# Mainboard.net
KiCad netlist of a schematic drawn in Altium Designer
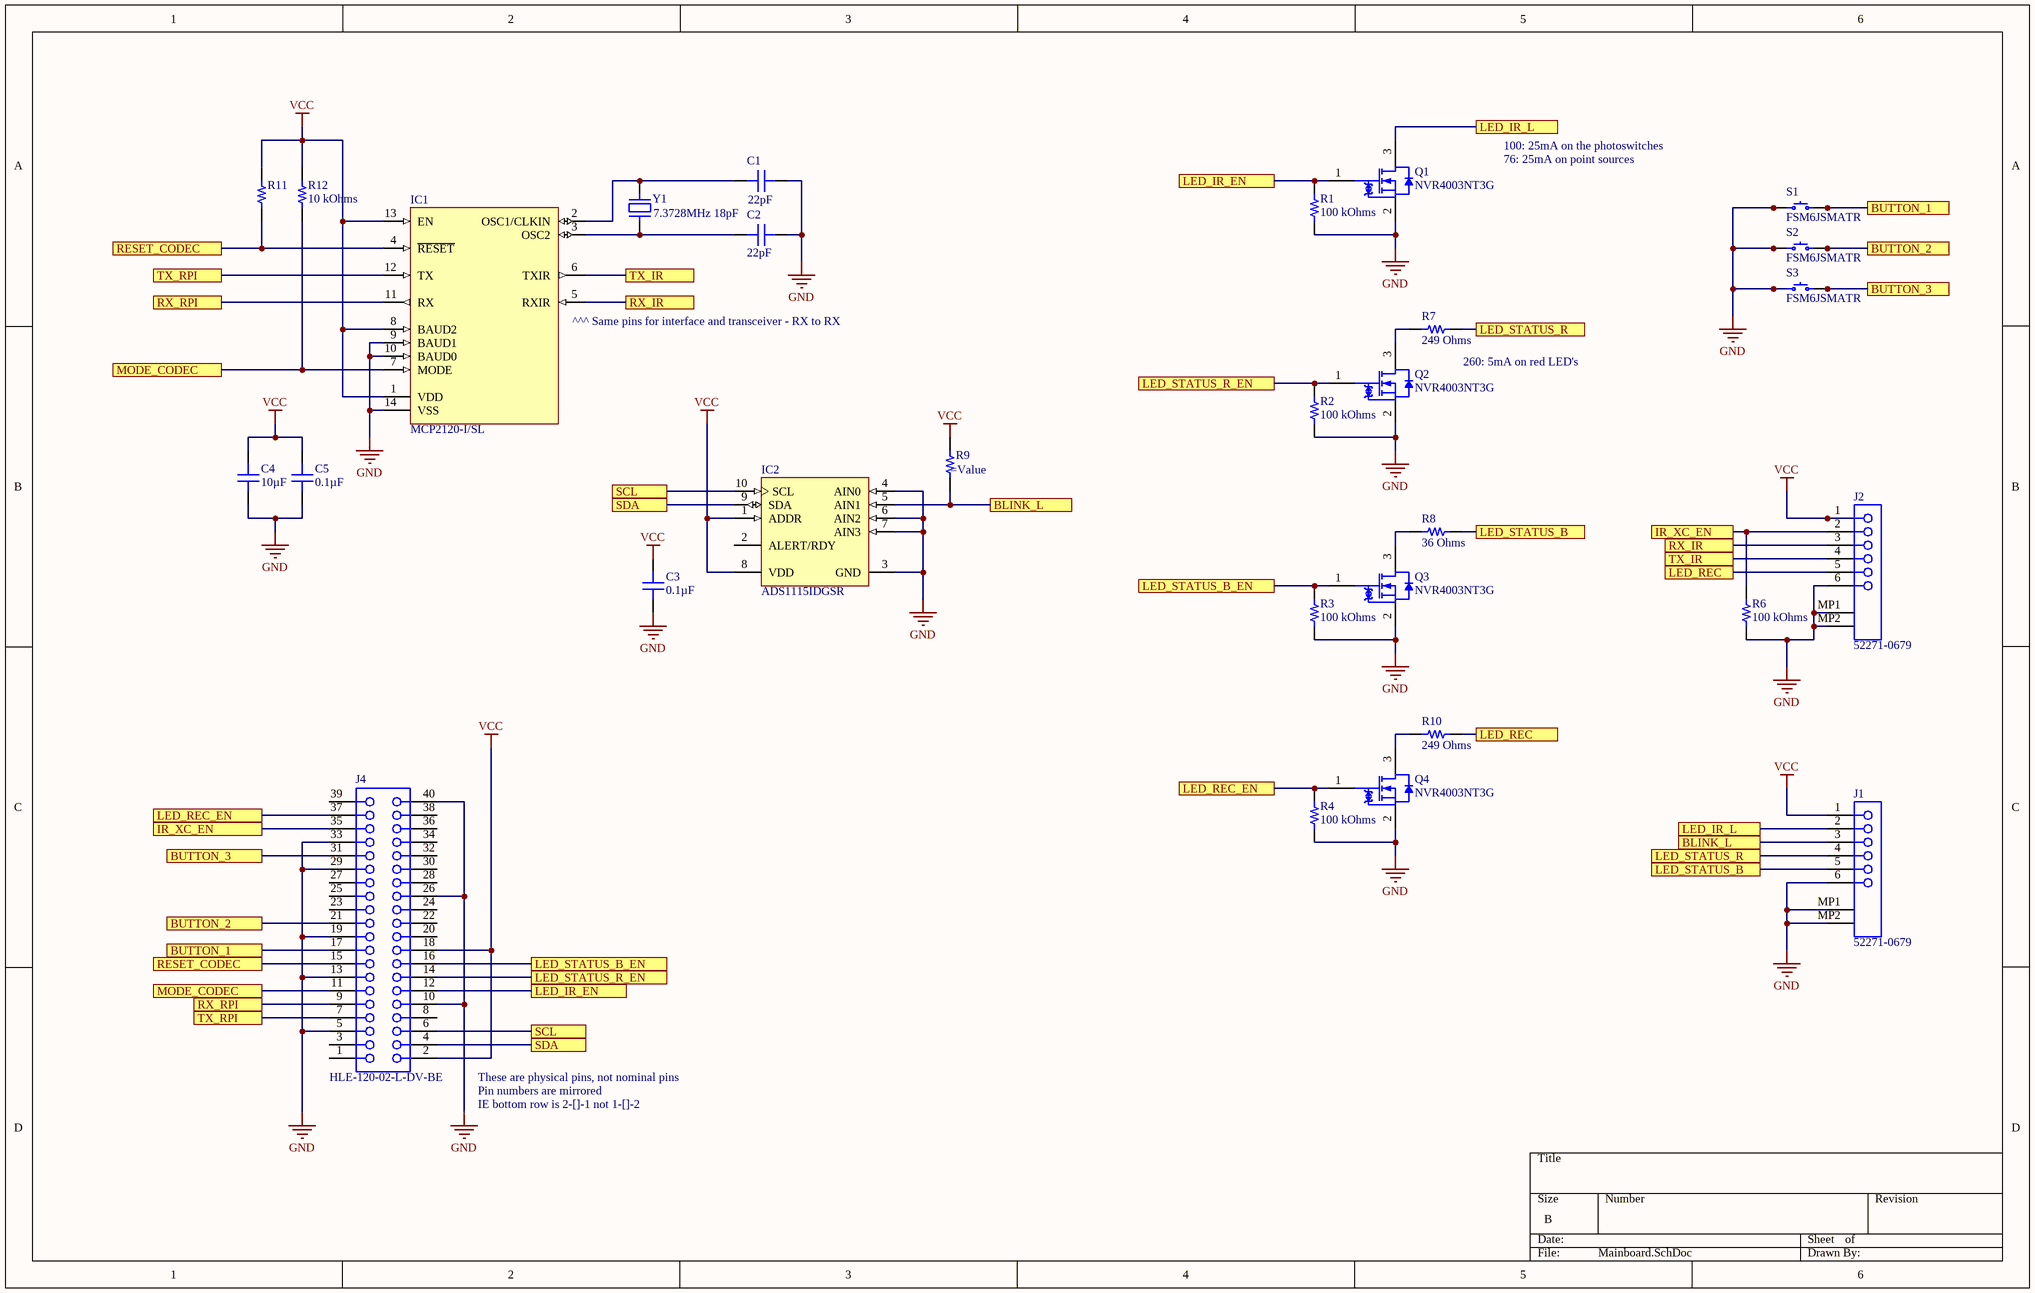
[diagram p0: Mainboard.SchDoc]

(export (version "E")
  (design (tool "Eeschema 10.0.6"))
  (components
    (comp (ref "C1")
      (value "22pF")
      (footprint "CAP 0603_1608")
      (description "CAP CER 22PF 16V C0G/NP0 0603")
      (fields (field (name "PART NUMBER") "885012006019") (field (name "MANUFACTURER") "Würth Elektronik"))
      (libsource (lib "Celestial Altium Library - altium_library") (part "Capacitor"))
    )
    (comp (ref "C2")
      (value "22pF")
      (footprint "CAP 0603_1608")
      (description "CAP CER 22PF 16V C0G/NP0 0603")
      (fields (field (name "PART NUMBER") "885012006019") (field (name "MANUFACTURER") "Würth Elektronik"))
      (libsource (lib "Celestial Altium Library - altium_library") (part "Capacitor"))
    )
    (comp (ref "C3")
      (value "0.1µF")
      (footprint "CAP 0603_1608")
      (description "CAP CER 0.1UF 50V X7R 0603")
      (fields (field (name "PART NUMBER") "C0603C104K5RAC7411") (field (name "MANUFACTURER") "KEMET"))
      (libsource (lib "Celestial Altium Library - altium_library") (part "Capacitor"))
    )
    (comp (ref "C4")
      (value "10µF")
      (footprint "CAP 1206_3216 - 1.0MM")
      (description "CAP CER 10UF 16V X5R 1206")
      (fields (field (name "PART NUMBER") "EMK316BJ106MD-T") (field (name "MANUFACTURER") "Taiyo Yuden"))
      (libsource (lib "Celestial Altium Library - altium_library") (part "Capacitor"))
    )
    (comp (ref "C5")
      (value "0.1µF")
      (footprint "CAP 0603_1608")
      (description "CAP CER 0.1UF 50V X7R 0603")
      (fields (field (name "PART NUMBER") "C0603C104K5RAC7411") (field (name "MANUFACTURER") "KEMET"))
      (libsource (lib "Celestial Altium Library - altium_library") (part "Capacitor"))
    )
    (comp (ref "IC1")
      (value "MCP2120-I/SL")
      (footprint "SOIC-SL14_N")
      (description "Infrared Encoder/Decoder, 14-Pin SOIC, Industrial Temperature")
      (fields (field (name "MANUFACTURER") "Microchip"))
      (libsource (lib "Microchip Interface") (part "MCP2120-I/SL"))
    )
    (comp (ref "IC2")
      (value "ADS1115IDGSR")
      (footprint "TI-DGS10_N")
      (fields (field (name "MANUFACTURER") "Texas Instruments"))
      (libsource (lib "TI Data Converters Analog to Digital Converter") (part "ADS1115IDGSR"))
    )
    (comp (ref "J1")
      (value "52271-0679")
      (footprint "MOLX-52271-0679")
      (fields (field (name "MANUFACTURER") "Molex"))
      (libsource (lib "Molex FFC - FPC Connectors (SMT)") (part "52271-0679"))
    )
    (comp (ref "J2")
      (value "52271-0679")
      (footprint "MOLX-52271-0679")
      (fields (field (name "MANUFACTURER") "Molex"))
      (libsource (lib "Molex FFC - FPC Connectors (SMT)") (part "52271-0679"))
    )
    (comp (ref "J4")
      (value "HLE-120-02-L-DV-BE")
      (footprint "SMTC-HLE-120-02-X-DV-BE")
      (fields (field (name "MANUFACTURER") "Samtec"))
      (libsource (lib "Samtec_2,54_mm_Pitch_Socket_Strips") (part "HLE-120-02-L-DV-BE"))
    )
    (comp (ref "Q1")
      (value "NVR4003NT3G")
      (footprint "ONSC-SOT-23-3-318-08_V")
      (description "Small Signal MOSFET, 30 V, 0.56 A, Single N-Channel, 3-Pin SOT-23, Pb-Free, Tape and Reel")
      (fields (field (name "MANUFACTURER") "On Semiconductor"))
      (libsource (lib "ON Semi MOSFETs") (part "NVR4003NT3G"))
    )
    (comp (ref "Q2")
      (value "NVR4003NT3G")
      (footprint "ONSC-SOT-23-3-318-08_V")
      (description "Small Signal MOSFET, 30 V, 0.56 A, Single N-Channel, 3-Pin SOT-23, Pb-Free, Tape and Reel")
      (fields (field (name "MANUFACTURER") "On Semiconductor"))
      (libsource (lib "ON Semi MOSFETs") (part "NVR4003NT3G"))
    )
    (comp (ref "Q3")
      (value "NVR4003NT3G")
      (footprint "ONSC-SOT-23-3-318-08_V")
      (description "Small Signal MOSFET, 30 V, 0.56 A, Single N-Channel, 3-Pin SOT-23, Pb-Free, Tape and Reel")
      (fields (field (name "MANUFACTURER") "On Semiconductor"))
      (libsource (lib "ON Semi MOSFETs") (part "NVR4003NT3G"))
    )
    (comp (ref "Q4")
      (value "NVR4003NT3G")
      (footprint "ONSC-SOT-23-3-318-08_V")
      (description "Small Signal MOSFET, 30 V, 0.56 A, Single N-Channel, 3-Pin SOT-23, Pb-Free, Tape and Reel")
      (fields (field (name "MANUFACTURER") "On Semiconductor"))
      (libsource (lib "ON Semi MOSFETs") (part "NVR4003NT3G"))
    )
    (comp (ref "R1")
      (value "100 kOhms")
      (footprint "RES 0603_1608")
      (description "RES SMD 100K OHM 0.1% 1/16W 0603")
      (fields
        (field (name "PART NUMBER") "CPF0603B100KE")
        (field (name "MANUFACTURER") "TE Connectivity Passive Product")
      )
      (libsource (lib "Celestial Altium Library - altium_library") (part "Resistor"))
    )
    (comp (ref "R2")
      (value "100 kOhms")
      (footprint "RES 0603_1608")
      (description "RES SMD 100K OHM 0.1% 1/16W 0603")
      (fields
        (field (name "PART NUMBER") "CPF0603B100KE")
        (field (name "MANUFACTURER") "TE Connectivity Passive Product")
      )
      (libsource (lib "Celestial Altium Library - altium_library") (part "Resistor"))
    )
    (comp (ref "R3")
      (value "100 kOhms")
      (footprint "RES 0603_1608")
      (description "RES SMD 100K OHM 0.1% 1/16W 0603")
      (fields
        (field (name "PART NUMBER") "CPF0603B100KE")
        (field (name "MANUFACTURER") "TE Connectivity Passive Product")
      )
      (libsource (lib "Celestial Altium Library - altium_library") (part "Resistor"))
    )
    (comp (ref "R4")
      (value "100 kOhms")
      (footprint "RES 0603_1608")
      (description "RES SMD 100K OHM 0.1% 1/16W 0603")
      (fields
        (field (name "PART NUMBER") "CPF0603B100KE")
        (field (name "MANUFACTURER") "TE Connectivity Passive Product")
      )
      (libsource (lib "Celestial Altium Library - altium_library") (part "Resistor"))
    )
    (comp (ref "R6")
      (value "100 kOhms")
      (footprint "RES 0603_1608")
      (description "RES SMD 100K OHM 0.1% 1/16W 0603")
      (fields
        (field (name "PART NUMBER") "CPF0603B100KE")
        (field (name "MANUFACTURER") "TE Connectivity Passive Product")
      )
      (libsource (lib "Celestial Altium Library - altium_library") (part "Resistor"))
    )
    (comp (ref "R7")
      (value "249 Ohms")
      (footprint "RES 0603_1608")
      (description "RES SMD 249 OHM 1% 1/10W 0603")
      (fields
        (field (name "PART NUMBER") "ERJ-3EKF2490V")
        (field (name "MANUFACTURER") "Panasonic Electronic Components")
      )
      (libsource (lib "Celestial Altium Library - altium_library") (part "Resistor"))
    )
    (comp (ref "R8")
      (value "36 Ohms")
      (footprint "RES 0603_1608")
      (description "RES 36 OHM 1% 1/8W 0603")
      (fields
        (field (name "PART NUMBER") "RK73H1JTTD36R0F")
        (field (name "MANUFACTURER") "KOA Speer Electronics, Inc.")
      )
      (libsource (lib "Celestial Altium Library - altium_library") (part "Resistor"))
    )
    (comp (ref "R9")
      (value "~")
      (footprint "RES 0603_1608")
      (description "RES 10K OHM 0.1% 1/16W 0603")
      (fields
        (field (name "PART NUMBER") "RNCS0603BKE10K0")
        (field (name "MANUFACTURER") "Stackpole Electronics Inc")
      )
      (libsource (lib "Celestial Altium Library - altium_library") (part "Resistor"))
    )
    (comp (ref "R10")
      (value "249 Ohms")
      (footprint "RES 0603_1608")
      (description "RES SMD 249 OHM 1% 1/10W 0603")
      (fields
        (field (name "PART NUMBER") "ERJ-3EKF2490V")
        (field (name "MANUFACTURER") "Panasonic Electronic Components")
      )
      (libsource (lib "Celestial Altium Library - altium_library") (part "Resistor"))
    )
    (comp (ref "R11")
      (value "~")
      (footprint "RES 0603_1608")
      (description "RES 10K OHM 0.1% 1/16W 0603")
      (fields
        (field (name "PART NUMBER") "RNCS0603BKE10K0")
        (field (name "MANUFACTURER") "Stackpole Electronics Inc")
      )
      (libsource (lib "Celestial Altium Library - altium_library") (part "Resistor"))
    )
    (comp (ref "R12")
      (value "10 kOhms")
      (footprint "RES 0603_1608")
      (description "RES 10K OHM 0.1% 1/16W 0603")
      (fields
        (field (name "PART NUMBER") "RNCS0603BKE10K0")
        (field (name "MANUFACTURER") "Stackpole Electronics Inc")
      )
      (libsource (lib "Celestial Altium Library - altium_library") (part "Resistor"))
    )
    (comp (ref "S1")
      (value "FSM6JSMATR")
      (footprint "TE FSM6JSMA")
      (description "SWITCH TACTILE SPST-NO 0.05A 24V")
      (fields (field (name "MANUFACTURER") "TE Connectivity ALCOSWITCH Switches"))
      (libsource (lib "Celestial Altium Library - altium_library") (part "SPST-NO 4 PIN"))
    )
    (comp (ref "S2")
      (value "FSM6JSMATR")
      (footprint "TE FSM6JSMA")
      (description "SWITCH TACTILE SPST-NO 0.05A 24V")
      (fields (field (name "MANUFACTURER") "TE Connectivity ALCOSWITCH Switches"))
      (libsource (lib "Celestial Altium Library - altium_library") (part "SPST-NO 4 PIN"))
    )
    (comp (ref "S3")
      (value "FSM6JSMATR")
      (footprint "TE FSM6JSMA")
      (description "SWITCH TACTILE SPST-NO 0.05A 24V")
      (fields (field (name "MANUFACTURER") "TE Connectivity ALCOSWITCH Switches"))
      (libsource (lib "Celestial Altium Library - altium_library") (part "SPST-NO 4 PIN"))
    )
    (comp (ref "Y1")
      (value "7.3728MHz 18pF")
      (footprint "HC-49 PTH")
      (description "Standard crystal")
      (libsource (lib "Voidstar Passives") (part "Xtal"))
    )
  )
  (nets
    (net (code "1") (name "/BLINK_L") (class "Default")
      (node (ref "IC2") (pin "5") (pinfunction "AIN1_5") (pintype "input"))
      (node (ref "J1") (pin "3") (pinfunction "3_3") (pintype "passive"))
      (node (ref "R9") (pin "1") (pinfunction "1_1") (pintype "passive"))
    )
    (net (code "2") (name "/BUTTON_1") (class "Default")
      (node (ref "J4") (pin "17") (pinfunction "17_17") (pintype "passive"))
      (node (ref "S1") (pin "3") (pinfunction "3_3") (pintype "passive"))
      (node (ref "S1") (pin "4") (pinfunction "4_4") (pintype "passive"))
    )
    (net (code "3") (name "/BUTTON_2") (class "Default")
      (node (ref "J4") (pin "21") (pinfunction "21_21") (pintype "passive"))
      (node (ref "S2") (pin "3") (pinfunction "3_3") (pintype "passive"))
      (node (ref "S2") (pin "4") (pinfunction "4_4") (pintype "passive"))
    )
    (net (code "4") (name "/BUTTON_3") (class "Default")
      (node (ref "J4") (pin "31") (pinfunction "31_31") (pintype "passive"))
      (node (ref "S3") (pin "3") (pinfunction "3_3") (pintype "passive"))
      (node (ref "S3") (pin "4") (pinfunction "4_4") (pintype "passive"))
    )
    (net (code "5") (name "/IR_XC_EN") (class "Default")
      (node (ref "J2") (pin "2") (pinfunction "2_2") (pintype "passive"))
      (node (ref "J4") (pin "35") (pinfunction "35_35") (pintype "passive"))
      (node (ref "R6") (pin "2") (pinfunction "2_2") (pintype "passive"))
    )
    (net (code "6") (name "/LED_IR_EN") (class "Default")
      (node (ref "J4") (pin "12") (pinfunction "12_12") (pintype "passive"))
      (node (ref "Q1") (pin "1") (pinfunction "G_1") (pintype "passive"))
      (node (ref "R1") (pin "2") (pinfunction "2_2") (pintype "passive"))
    )
    (net (code "7") (name "/LED_IR_L") (class "Default")
      (node (ref "J1") (pin "2") (pinfunction "2_2") (pintype "passive"))
      (node (ref "Q1") (pin "3") (pinfunction "D_3") (pintype "passive"))
    )
    (net (code "8") (name "/LED_REC") (class "Default")
      (node (ref "J2") (pin "5") (pinfunction "5_5") (pintype "passive"))
      (node (ref "R10") (pin "2") (pinfunction "2_2") (pintype "passive"))
    )
    (net (code "9") (name "/LED_REC_EN") (class "Default")
      (node (ref "J4") (pin "37") (pinfunction "37_37") (pintype "passive"))
      (node (ref "Q4") (pin "1") (pinfunction "G_1") (pintype "passive"))
      (node (ref "R4") (pin "2") (pinfunction "2_2") (pintype "passive"))
    )
    (net (code "10") (name "/LED_STATUS_B") (class "Default")
      (node (ref "J1") (pin "5") (pinfunction "5_5") (pintype "passive"))
      (node (ref "R8") (pin "2") (pinfunction "2_2") (pintype "passive"))
    )
    (net (code "11") (name "/LED_STATUS_B_EN") (class "Default")
      (node (ref "J4") (pin "16") (pinfunction "16_16") (pintype "passive"))
      (node (ref "Q3") (pin "1") (pinfunction "G_1") (pintype "passive"))
      (node (ref "R3") (pin "2") (pinfunction "2_2") (pintype "passive"))
    )
    (net (code "12") (name "/LED_STATUS_R") (class "Default")
      (node (ref "J1") (pin "4") (pinfunction "4_4") (pintype "passive"))
      (node (ref "R7") (pin "2") (pinfunction "2_2") (pintype "passive"))
    )
    (net (code "13") (name "/LED_STATUS_R_EN") (class "Default")
      (node (ref "J4") (pin "14") (pinfunction "14_14") (pintype "passive"))
      (node (ref "Q2") (pin "1") (pinfunction "G_1") (pintype "passive"))
      (node (ref "R2") (pin "2") (pinfunction "2_2") (pintype "passive"))
    )
    (net (code "14") (name "/MODE_CODEC") (class "Default")
      (node (ref "IC1") (pin "7") (pinfunction "MODE_7") (pintype "input"))
      (node (ref "J4") (pin "11") (pinfunction "11_11") (pintype "passive"))
      (node (ref "R12") (pin "1") (pinfunction "1_1") (pintype "passive"))
    )
    (net (code "15") (name "/RESET_CODEC") (class "Default")
      (node (ref "IC1") (pin "4") (pinfunction "~{RESET}_4") (pintype "input"))
      (node (ref "J4") (pin "15") (pinfunction "15_15") (pintype "passive"))
      (node (ref "R11") (pin "1") (pinfunction "1_1") (pintype "passive"))
    )
    (net (code "16") (name "/RX_IR") (class "Default")
      (node (ref "IC1") (pin "5") (pinfunction "RXIR_5") (pintype "input"))
      (node (ref "J2") (pin "3") (pinfunction "3_3") (pintype "passive"))
    )
    (net (code "17") (name "/RX_RPI") (class "Default")
      (node (ref "IC1") (pin "11") (pinfunction "RX_11") (pintype "output"))
      (node (ref "J4") (pin "9") (pinfunction "9_9") (pintype "passive"))
    )
    (net (code "18") (name "/SCL") (class "Default")
      (node (ref "IC2") (pin "10") (pinfunction "SCL_10") (pintype "input"))
      (node (ref "J4") (pin "6") (pinfunction "6_6") (pintype "passive"))
    )
    (net (code "19") (name "/SDA") (class "Default")
      (node (ref "IC2") (pin "9") (pinfunction "SDA_9") (pintype "bidirectional"))
      (node (ref "J4") (pin "4") (pinfunction "4_4") (pintype "passive"))
    )
    (net (code "20") (name "/TX_IR") (class "Default")
      (node (ref "IC1") (pin "6") (pinfunction "TXIR_6") (pintype "output"))
      (node (ref "J2") (pin "4") (pinfunction "4_4") (pintype "passive"))
    )
    (net (code "21") (name "/TX_RPI") (class "Default")
      (node (ref "IC1") (pin "12") (pinfunction "TX_12") (pintype "input"))
      (node (ref "J4") (pin "7") (pinfunction "7_7") (pintype "passive"))
    )
    (net (code "22") (name "GND") (class "Default")
      (node (ref "C1") (pin "2") (pinfunction "2_2") (pintype "passive"))
      (node (ref "C2") (pin "2") (pinfunction "2_2") (pintype "passive"))
      (node (ref "C3") (pin "1") (pinfunction "1_1") (pintype "passive"))
      (node (ref "C4") (pin "1") (pinfunction "1_1") (pintype "passive"))
      (node (ref "C5") (pin "1") (pinfunction "1_1") (pintype "passive"))
      (node (ref "IC1") (pin "10") (pinfunction "BAUD0_10") (pintype "input"))
      (node (ref "IC1") (pin "14") (pinfunction "VSS_14") (pintype "power_in"))
      (node (ref "IC1") (pin "9") (pinfunction "BAUD1_9") (pintype "input"))
      (node (ref "IC2") (pin "3") (pinfunction "GND_3") (pintype "power_in"))
      (node (ref "IC2") (pin "4") (pinfunction "AIN0_4") (pintype "input"))
      (node (ref "IC2") (pin "6") (pinfunction "AIN2_6") (pintype "input"))
      (node (ref "IC2") (pin "7") (pinfunction "AIN3_7") (pintype "input"))
      (node (ref "J1") (pin "6") (pinfunction "6_6") (pintype "passive"))
      (node (ref "J1") (pin "MP1") (pinfunction "MP1_MP1") (pintype "passive"))
      (node (ref "J1") (pin "MP2") (pinfunction "MP2_MP2") (pintype "passive"))
      (node (ref "J2") (pin "6") (pinfunction "6_6") (pintype "passive"))
      (node (ref "J2") (pin "MP1") (pinfunction "MP1_MP1") (pintype "passive"))
      (node (ref "J2") (pin "MP2") (pinfunction "MP2_MP2") (pintype "passive"))
      (node (ref "J4") (pin "10") (pinfunction "10_10") (pintype "passive"))
      (node (ref "J4") (pin "13") (pinfunction "13_13") (pintype "passive"))
      (node (ref "J4") (pin "19") (pinfunction "19_19") (pintype "passive"))
      (node (ref "J4") (pin "26") (pinfunction "26_26") (pintype "passive"))
      (node (ref "J4") (pin "29") (pinfunction "29_29") (pintype "passive"))
      (node (ref "J4") (pin "33") (pinfunction "33_33") (pintype "passive"))
      (node (ref "J4") (pin "40") (pinfunction "40_40") (pintype "passive"))
      (node (ref "J4") (pin "5") (pinfunction "5_5") (pintype "passive"))
      (node (ref "Q1") (pin "2") (pinfunction "S_2") (pintype "passive"))
      (node (ref "Q2") (pin "2") (pinfunction "S_2") (pintype "passive"))
      (node (ref "Q3") (pin "2") (pinfunction "S_2") (pintype "passive"))
      (node (ref "Q4") (pin "2") (pinfunction "S_2") (pintype "passive"))
      (node (ref "R1") (pin "1") (pinfunction "1_1") (pintype "passive"))
      (node (ref "R2") (pin "1") (pinfunction "1_1") (pintype "passive"))
      (node (ref "R3") (pin "1") (pinfunction "1_1") (pintype "passive"))
      (node (ref "R4") (pin "1") (pinfunction "1_1") (pintype "passive"))
      (node (ref "R6") (pin "1") (pinfunction "1_1") (pintype "passive"))
      (node (ref "S1") (pin "1") (pinfunction "1_1") (pintype "passive"))
      (node (ref "S1") (pin "2") (pinfunction "2_2") (pintype "passive"))
      (node (ref "S2") (pin "1") (pinfunction "1_1") (pintype "passive"))
      (node (ref "S2") (pin "2") (pinfunction "2_2") (pintype "passive"))
      (node (ref "S3") (pin "1") (pinfunction "1_1") (pintype "passive"))
      (node (ref "S3") (pin "2") (pinfunction "2_2") (pintype "passive"))
    )
    (net (code "23") (name "Net-(IC1-OSC1{slash}CLKIN)") (class "Default")
      (node (ref "C1") (pin "1") (pinfunction "1_1") (pintype "passive"))
      (node (ref "IC1") (pin "2") (pinfunction "OSC1/CLKIN_2") (pintype "bidirectional"))
      (node (ref "Y1") (pin "2") (pinfunction "2_2") (pintype "passive"))
    )
    (net (code "24") (name "Net-(IC1-OSC2)") (class "Default")
      (node (ref "C2") (pin "1") (pinfunction "1_1") (pintype "passive"))
      (node (ref "IC1") (pin "3") (pinfunction "OSC2_3") (pintype "bidirectional"))
      (node (ref "Y1") (pin "1") (pinfunction "1_1") (pintype "passive"))
    )
    (net (code "25") (name "Net-(Q2-D)") (class "Default")
      (node (ref "Q2") (pin "3") (pinfunction "D_3") (pintype "passive"))
      (node (ref "R7") (pin "1") (pinfunction "1_1") (pintype "passive"))
    )
    (net (code "26") (name "Net-(Q3-D)") (class "Default")
      (node (ref "Q3") (pin "3") (pinfunction "D_3") (pintype "passive"))
      (node (ref "R8") (pin "1") (pinfunction "1_1") (pintype "passive"))
    )
    (net (code "27") (name "Net-(Q4-D)") (class "Default")
      (node (ref "Q4") (pin "3") (pinfunction "D_3") (pintype "passive"))
      (node (ref "R10") (pin "1") (pinfunction "1_1") (pintype "passive"))
    )
    (net (code "28") (name "VCC") (class "Default")
      (node (ref "C3") (pin "2") (pinfunction "2_2") (pintype "passive"))
      (node (ref "C4") (pin "2") (pinfunction "2_2") (pintype "passive"))
      (node (ref "C5") (pin "2") (pinfunction "2_2") (pintype "passive"))
      (node (ref "IC1") (pin "1") (pinfunction "VDD_1") (pintype "power_in"))
      (node (ref "IC1") (pin "13") (pinfunction "EN_13") (pintype "input"))
      (node (ref "IC1") (pin "8") (pinfunction "BAUD2_8") (pintype "input"))
      (node (ref "IC2") (pin "1") (pinfunction "ADDR_1") (pintype "input"))
      (node (ref "IC2") (pin "8") (pinfunction "VDD_8") (pintype "power_in"))
      (node (ref "J1") (pin "1") (pinfunction "1_1") (pintype "passive"))
      (node (ref "J2") (pin "1") (pinfunction "1_1") (pintype "passive"))
      (node (ref "J4") (pin "18") (pinfunction "18_18") (pintype "passive"))
      (node (ref "J4") (pin "2") (pinfunction "2_2") (pintype "passive"))
      (node (ref "R11") (pin "2") (pinfunction "2_2") (pintype "passive"))
      (node (ref "R12") (pin "2") (pinfunction "2_2") (pintype "passive"))
      (node (ref "R9") (pin "2") (pinfunction "2_2") (pintype "passive"))
    )
    (net (code "29") (name "unconnected-(IC2-ALERT{slash}RDY-Pad2)") (class "Default")
      (node (ref "IC2") (pin "2") (pinfunction "ALERT/RDY_2") (pintype "open_collector"))
    )
    (net (code "30") (name "unconnected-(J4-Pad1)") (class "Default")
      (node (ref "J4") (pin "1") (pinfunction "1_1") (pintype "passive"))
    )
    (net (code "31") (name "unconnected-(J4-Pad3)") (class "Default")
      (node (ref "J4") (pin "3") (pinfunction "3_3") (pintype "passive"))
    )
    (net (code "32") (name "unconnected-(J4-Pad8)") (class "Default")
      (node (ref "J4") (pin "8") (pinfunction "8_8") (pintype "passive"))
    )
    (net (code "33") (name "unconnected-(J4-Pad20)") (class "Default")
      (node (ref "J4") (pin "20") (pinfunction "20_20") (pintype "passive"))
    )
    (net (code "34") (name "unconnected-(J4-Pad22)") (class "Default")
      (node (ref "J4") (pin "22") (pinfunction "22_22") (pintype "passive"))
    )
    (net (code "35") (name "unconnected-(J4-Pad23)") (class "Default")
      (node (ref "J4") (pin "23") (pinfunction "23_23") (pintype "passive"))
    )
    (net (code "36") (name "unconnected-(J4-Pad24)") (class "Default")
      (node (ref "J4") (pin "24") (pinfunction "24_24") (pintype "passive"))
    )
    (net (code "37") (name "unconnected-(J4-Pad25)") (class "Default")
      (node (ref "J4") (pin "25") (pinfunction "25_25") (pintype "passive"))
    )
    (net (code "38") (name "unconnected-(J4-Pad27)") (class "Default")
      (node (ref "J4") (pin "27") (pinfunction "27_27") (pintype "passive"))
    )
    (net (code "39") (name "unconnected-(J4-Pad28)") (class "Default")
      (node (ref "J4") (pin "28") (pinfunction "28_28") (pintype "passive"))
    )
    (net (code "40") (name "unconnected-(J4-Pad30)") (class "Default")
      (node (ref "J4") (pin "30") (pinfunction "30_30") (pintype "passive"))
    )
    (net (code "41") (name "unconnected-(J4-Pad32)") (class "Default")
      (node (ref "J4") (pin "32") (pinfunction "32_32") (pintype "passive"))
    )
    (net (code "42") (name "unconnected-(J4-Pad34)") (class "Default")
      (node (ref "J4") (pin "34") (pinfunction "34_34") (pintype "passive"))
    )
    (net (code "43") (name "unconnected-(J4-Pad36)") (class "Default")
      (node (ref "J4") (pin "36") (pinfunction "36_36") (pintype "passive"))
    )
    (net (code "44") (name "unconnected-(J4-Pad38)") (class "Default")
      (node (ref "J4") (pin "38") (pinfunction "38_38") (pintype "passive"))
    )
    (net (code "45") (name "unconnected-(J4-Pad39)") (class "Default")
      (node (ref "J4") (pin "39") (pinfunction "39_39") (pintype "passive"))
    )
  )
)
